# VisualightMicroDIY_03_gnd.net
KiCad netlist of a schematic drawn in EAGLE
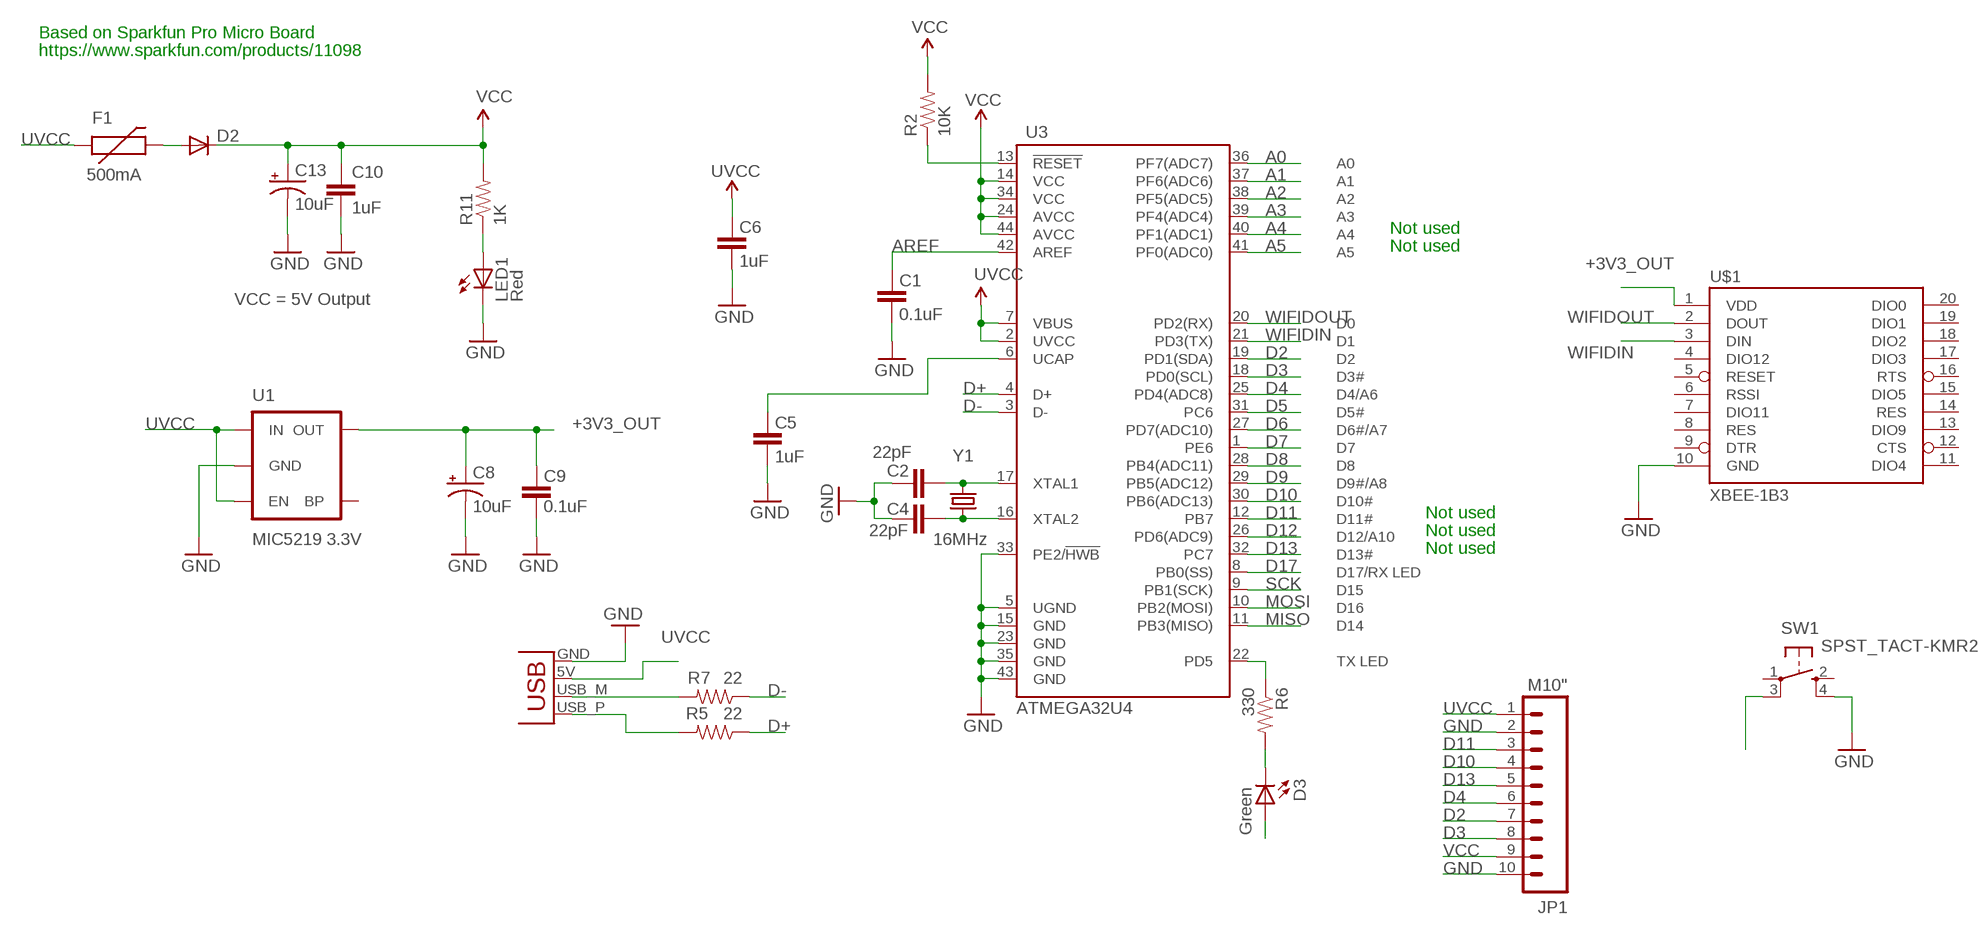
[diagram p0: schematic, sheet 1]

(export (version "E")
  (design (tool "Eeschema 10.0.6"))
  (components
    (comp (ref "C1")
      (value "0.1uF")
      (footprint "eagle-import:0402-CAP")
      (libsource (lib "eagle-import") (part "CAP0402-CAP"))
    )
    (comp (ref "C2")
      (value "22pF")
      (footprint "eagle-import:0402-CAP")
      (libsource (lib "eagle-import") (part "CAP0402-CAP"))
    )
    (comp (ref "C4")
      (value "22pF")
      (footprint "eagle-import:0402-CAP")
      (libsource (lib "eagle-import") (part "CAP0402-CAP"))
    )
    (comp (ref "C5")
      (value "1uF")
      (footprint "eagle-import:0402-CAP")
      (libsource (lib "eagle-import") (part "CAP0402-CAP"))
    )
    (comp (ref "C6")
      (value "1uF")
      (footprint "eagle-import:0402-CAP")
      (libsource (lib "eagle-import") (part "CAP0402-CAP"))
    )
    (comp (ref "C8")
      (value "10uF")
      (footprint "eagle-import:EIA3216")
      (libsource (lib "eagle-import") (part "CAP_POL1206"))
    )
    (comp (ref "C9")
      (value "0.1uF")
      (footprint "eagle-import:0402-CAP")
      (libsource (lib "eagle-import") (part "CAP0402-CAP"))
    )
    (comp (ref "C10")
      (value "1uF")
      (footprint "eagle-import:0402-CAP")
      (libsource (lib "eagle-import") (part "CAP0402-CAP"))
    )
    (comp (ref "C13")
      (value "10uF")
      (footprint "eagle-import:EIA3216")
      (libsource (lib "eagle-import") (part "CAP_POL1206"))
    )
    (comp (ref "D2")
      (value "DIODESOD")
      (footprint "eagle-import:SOD-323")
      (libsource (lib "eagle-import") (part "DIODESOD"))
    )
    (comp (ref "D3")
      (value "Green")
      (footprint "eagle-import:LED-0603")
      (libsource (lib "eagle-import") (part "LED0603"))
    )
    (comp (ref "F1")
      (value "500mA")
      (footprint "eagle-import:PTC-1206")
      (libsource (lib "eagle-import") (part "PTCSMD"))
    )
    (comp (ref "JP1")
      (value "M10\"")
      (footprint "eagle-import:1X10")
      (libsource (lib "eagle-import") (part "M10{dblquote}"))
    )
    (comp (ref "LED1")
      (value "Red")
      (footprint "eagle-import:LED-0603")
      (libsource (lib "eagle-import") (part "LED0603"))
    )
    (comp (ref "R2")
      (value "10K")
      (footprint "eagle-import:0402-RES")
      (libsource (lib "eagle-import") (part "RESISTOR0402-RES"))
    )
    (comp (ref "R5")
      (value "22")
      (footprint "eagle-import:0402-RES")
      (libsource (lib "eagle-import") (part "RESISTOR0402-RES"))
    )
    (comp (ref "R6")
      (value "330")
      (footprint "eagle-import:0402-RES")
      (libsource (lib "eagle-import") (part "RESISTOR0402-RES"))
    )
    (comp (ref "R7")
      (value "22")
      (footprint "eagle-import:0402-RES")
      (libsource (lib "eagle-import") (part "RESISTOR0402-RES"))
    )
    (comp (ref "R11")
      (value "1K")
      (footprint "eagle-import:0402-RES")
      (libsource (lib "eagle-import") (part "RESISTOR0402-RES"))
    )
    (comp (ref "SW1")
      (value "SPST_TACT-KMR2")
      (footprint "eagle-import:KMR2")
      (libsource (lib "eagle-import") (part "SPST_TACT-KMR2"))
    )
    (comp (ref "U$1")
      (value "XBEE-1B3")
      (footprint "eagle-import:XBEE-SMD")
      (libsource (lib "eagle-import") (part "XBEE-1B3"))
    )
    (comp (ref "U1")
      (value "MIC5219 3.3V")
      (footprint "eagle-import:SOT23-5")
      (libsource (lib "eagle-import") (part "V_REG_MIC52193.3V"))
    )
    (comp (ref "U3")
      (value "ATMEGA32U4")
      (footprint "eagle-import:SPARKFUN-DIGITALIC_TQFP44")
      (libsource (lib "eagle-import") (part "ATMEGA32U4TQFP"))
    )
    (comp (ref "X2")
      (value "USBPCB")
      (footprint "eagle-import:USB-A-PCB")
      (libsource (lib "eagle-import") (part "USBPCB"))
    )
    (comp (ref "Y1")
      (value "16MHz")
      (footprint "eagle-import:CRYSTAL-SMD-5X3")
      (libsource (lib "eagle-import") (part "CRYSTAL5X3"))
    )
  )
  (nets
    (net (code "1") (name "/+3V3_OUT") (class "Default")
      (node (ref "C8") (pin "A") (pinfunction "+_A") (pintype "passive"))
      (node (ref "C9") (pin "2") (pinfunction "2_2") (pintype "passive"))
      (node (ref "U$1") (pin "1") (pinfunction "VDD_1") (pintype "power_in"))
      (node (ref "U1") (pin "5") (pinfunction "OUT_5") (pintype "passive"))
    )
    (net (code "2") (name "/A0") (class "Default")
      (node (ref "U3") (pin "36") (pinfunction "PF7(ADC7)_36") (pintype "bidirectional"))
    )
    (net (code "3") (name "/A1") (class "Default")
      (node (ref "U3") (pin "37") (pinfunction "PF6(ADC6)_37") (pintype "bidirectional"))
    )
    (net (code "4") (name "/A2") (class "Default")
      (node (ref "U3") (pin "38") (pinfunction "PF5(ADC5)_38") (pintype "bidirectional"))
    )
    (net (code "5") (name "/A3") (class "Default")
      (node (ref "U3") (pin "39") (pinfunction "PF4(ADC4)_39") (pintype "bidirectional"))
    )
    (net (code "6") (name "/A4") (class "Default")
      (node (ref "U3") (pin "40") (pinfunction "PF1(ADC1)_40") (pintype "bidirectional"))
    )
    (net (code "7") (name "/A5") (class "Default")
      (node (ref "U3") (pin "41") (pinfunction "PF0(ADC0)_41") (pintype "bidirectional"))
    )
    (net (code "8") (name "/AREF") (class "Default")
      (node (ref "C1") (pin "2") (pinfunction "2_2") (pintype "passive"))
      (node (ref "U3") (pin "42") (pinfunction "AREF_42") (pintype "bidirectional"))
    )
    (net (code "9") (name "/D+") (class "Default")
      (node (ref "R5") (pin "1") (pinfunction "1_1") (pintype "passive"))
      (node (ref "U3") (pin "4") (pinfunction "D+_4") (pintype "bidirectional"))
    )
    (net (code "10") (name "/D-") (class "Default")
      (node (ref "R7") (pin "1") (pinfunction "1_1") (pintype "passive"))
      (node (ref "U3") (pin "3") (pinfunction "D-_3") (pintype "bidirectional"))
    )
    (net (code "11") (name "/D2") (class "Default")
      (node (ref "JP1") (pin "7") (pinfunction "7_7") (pintype "passive"))
      (node (ref "U3") (pin "19") (pinfunction "PD1(SDA)_19") (pintype "bidirectional"))
    )
    (net (code "12") (name "/D3") (class "Default")
      (node (ref "JP1") (pin "8") (pinfunction "8_8") (pintype "passive"))
      (node (ref "U3") (pin "18") (pinfunction "PD0(SCL)_18") (pintype "bidirectional"))
    )
    (net (code "13") (name "/D4") (class "Default")
      (node (ref "JP1") (pin "6") (pinfunction "6_6") (pintype "passive"))
      (node (ref "U3") (pin "25") (pinfunction "PD4(ADC8)_25") (pintype "bidirectional"))
    )
    (net (code "14") (name "/D5") (class "Default")
      (node (ref "U3") (pin "31") (pinfunction "PC6_31") (pintype "bidirectional"))
    )
    (net (code "15") (name "/D6") (class "Default")
      (node (ref "U3") (pin "27") (pinfunction "PD7(ADC10)_27") (pintype "bidirectional"))
    )
    (net (code "16") (name "/D7") (class "Default")
      (node (ref "SW1") (pin "3") (pinfunction "P1_3") (pintype "passive"))
      (node (ref "U3") (pin "1") (pinfunction "PE6_1") (pintype "bidirectional"))
    )
    (net (code "17") (name "/D8") (class "Default")
      (node (ref "U3") (pin "28") (pinfunction "PB4(ADC11)_28") (pintype "bidirectional"))
    )
    (net (code "18") (name "/D9") (class "Default")
      (node (ref "U3") (pin "29") (pinfunction "PB5(ADC12)_29") (pintype "bidirectional"))
    )
    (net (code "19") (name "/D10") (class "Default")
      (node (ref "JP1") (pin "4") (pinfunction "4_4") (pintype "passive"))
      (node (ref "U3") (pin "30") (pinfunction "PB6(ADC13)_30") (pintype "bidirectional"))
    )
    (net (code "20") (name "/D11") (class "Default")
      (node (ref "JP1") (pin "3") (pinfunction "3_3") (pintype "passive"))
      (node (ref "U3") (pin "12") (pinfunction "PB7_12") (pintype "bidirectional"))
    )
    (net (code "21") (name "/D12") (class "Default")
      (node (ref "U3") (pin "26") (pinfunction "PD6(ADC9)_26") (pintype "bidirectional"))
    )
    (net (code "22") (name "/D13") (class "Default")
      (node (ref "JP1") (pin "5") (pinfunction "5_5") (pintype "passive"))
      (node (ref "U3") (pin "32") (pinfunction "PC7_32") (pintype "bidirectional"))
    )
    (net (code "23") (name "/D17") (class "Default")
      (node (ref "U3") (pin "8") (pinfunction "PB0(SS)_8") (pintype "bidirectional"))
    )
    (net (code "24") (name "/MISO") (class "Default")
      (node (ref "U3") (pin "11") (pinfunction "PB3(MISO)_11") (pintype "bidirectional"))
    )
    (net (code "25") (name "/MOSI") (class "Default")
      (node (ref "U3") (pin "10") (pinfunction "PB2(MOSI)_10") (pintype "bidirectional"))
    )
    (net (code "26") (name "/SCK") (class "Default")
      (node (ref "U3") (pin "9") (pinfunction "PB1(SCK)_9") (pintype "bidirectional"))
    )
    (net (code "27") (name "/WIFIDIN") (class "Default")
      (node (ref "U$1") (pin "3") (pinfunction "DIN_3") (pintype "input"))
      (node (ref "U3") (pin "21") (pinfunction "PD3(TX)_21") (pintype "bidirectional"))
    )
    (net (code "28") (name "/WIFIDOUT") (class "Default")
      (node (ref "U$1") (pin "2") (pinfunction "DOUT_2") (pintype "output"))
      (node (ref "U3") (pin "20") (pinfunction "PD2(RX)_20") (pintype "bidirectional"))
    )
    (net (code "29") (name "GND") (class "Default")
      (node (ref "C1") (pin "1") (pinfunction "1_1") (pintype "passive"))
      (node (ref "C10") (pin "2") (pinfunction "2_2") (pintype "passive"))
      (node (ref "C13") (pin "C") (pinfunction "-_C") (pintype "passive"))
      (node (ref "C2") (pin "2") (pinfunction "2_2") (pintype "passive"))
      (node (ref "C4") (pin "2") (pinfunction "2_2") (pintype "passive"))
      (node (ref "C5") (pin "1") (pinfunction "1_1") (pintype "passive"))
      (node (ref "C6") (pin "1") (pinfunction "1_1") (pintype "passive"))
      (node (ref "C8") (pin "C") (pinfunction "-_C") (pintype "passive"))
      (node (ref "C9") (pin "1") (pinfunction "1_1") (pintype "passive"))
      (node (ref "JP1") (pin "10") (pinfunction "10_10") (pintype "passive"))
      (node (ref "JP1") (pin "2") (pinfunction "2_2") (pintype "passive"))
      (node (ref "LED1") (pin "C") (pinfunction "C_C") (pintype "passive"))
      (node (ref "SW1") (pin "4") (pinfunction "S1_4") (pintype "passive"))
      (node (ref "U$1") (pin "10") (pinfunction "GND_10") (pintype "power_in"))
      (node (ref "U1") (pin "2") (pinfunction "GND_2") (pintype "input"))
      (node (ref "U3") (pin "15") (pinfunction "GND_15") (pintype "bidirectional"))
      (node (ref "U3") (pin "23") (pinfunction "GND_23") (pintype "bidirectional"))
      (node (ref "U3") (pin "33") (pinfunction "PE2/~{HWB}_33") (pintype "bidirectional"))
      (node (ref "U3") (pin "35") (pinfunction "GND_35") (pintype "bidirectional"))
      (node (ref "U3") (pin "43") (pinfunction "GND_43") (pintype "bidirectional"))
      (node (ref "U3") (pin "5") (pinfunction "UGND_5") (pintype "bidirectional"))
      (node (ref "X2") (pin "GND") (pinfunction "GND_GND") (pintype "bidirectional"))
    )
    (net (code "30") (name "Net-(D2-A)") (class "Default")
      (node (ref "D2") (pin "2") (pinfunction "A_2") (pintype "passive"))
      (node (ref "F1") (pin "2") (pinfunction "2_2") (pintype "bidirectional"))
    )
    (net (code "31") (name "Net-(D3-PadC)") (class "Default")
      (node (ref "D3") (pin "C") (pinfunction "C_C") (pintype "passive"))
      (node (ref "R6") (pin "2") (pinfunction "2_2") (pintype "passive"))
    )
    (net (code "32") (name "Net-(LED1-PadA)") (class "Default")
      (node (ref "LED1") (pin "A") (pinfunction "A_A") (pintype "passive"))
      (node (ref "R11") (pin "1") (pinfunction "1_1") (pintype "passive"))
    )
    (net (code "33") (name "Net-(U3-PD5)") (class "Default")
      (node (ref "R6") (pin "1") (pinfunction "1_1") (pintype "passive"))
      (node (ref "U3") (pin "22") (pinfunction "PD5_22") (pintype "bidirectional"))
    )
    (net (code "34") (name "Net-(U3-UCAP)") (class "Default")
      (node (ref "C5") (pin "2") (pinfunction "2_2") (pintype "passive"))
      (node (ref "U3") (pin "6") (pinfunction "UCAP_6") (pintype "bidirectional"))
    )
    (net (code "35") (name "Net-(U3-XTAL1)") (class "Default")
      (node (ref "C2") (pin "1") (pinfunction "1_1") (pintype "passive"))
      (node (ref "U3") (pin "17") (pinfunction "XTAL1_17") (pintype "bidirectional"))
      (node (ref "Y1") (pin "3") (pinfunction "2_3") (pintype "passive"))
    )
    (net (code "36") (name "Net-(U3-XTAL2)") (class "Default")
      (node (ref "C4") (pin "1") (pinfunction "1_1") (pintype "passive"))
      (node (ref "U3") (pin "16") (pinfunction "XTAL2_16") (pintype "bidirectional"))
      (node (ref "Y1") (pin "1") (pinfunction "1_1") (pintype "passive"))
    )
    (net (code "37") (name "Net-(U3-~{RESET})") (class "Default")
      (node (ref "R2") (pin "1") (pinfunction "1_1") (pintype "passive"))
      (node (ref "U3") (pin "13") (pinfunction "~{RESET}_13") (pintype "bidirectional"))
    )
    (net (code "38") (name "Net-(X2-D+)") (class "Default")
      (node (ref "R5") (pin "2") (pinfunction "2_2") (pintype "passive"))
      (node (ref "X2") (pin "USB_P") (pinfunction "D+_USB_P") (pintype "bidirectional"))
    )
    (net (code "39") (name "Net-(X2-D-)") (class "Default")
      (node (ref "R7") (pin "2") (pinfunction "2_2") (pintype "passive"))
      (node (ref "X2") (pin "USB_M") (pinfunction "D-_USB_M") (pintype "bidirectional"))
    )
    (net (code "40") (name "UVCC") (class "Default")
      (node (ref "C6") (pin "2") (pinfunction "2_2") (pintype "passive"))
      (node (ref "D3") (pin "A") (pinfunction "A_A") (pintype "passive"))
      (node (ref "F1") (pin "1") (pinfunction "1_1") (pintype "bidirectional"))
      (node (ref "JP1") (pin "1") (pinfunction "1_1") (pintype "passive"))
      (node (ref "U1") (pin "1") (pinfunction "IN_1") (pintype "input"))
      (node (ref "U1") (pin "3") (pinfunction "EN_3") (pintype "input"))
      (node (ref "U3") (pin "2") (pinfunction "UVCC_2") (pintype "bidirectional"))
      (node (ref "U3") (pin "7") (pinfunction "VBUS_7") (pintype "bidirectional"))
      (node (ref "X2") (pin "5V") (pinfunction "VBUS_5V") (pintype "bidirectional"))
    )
    (net (code "41") (name "VCC") (class "Default")
      (node (ref "C10") (pin "1") (pinfunction "1_1") (pintype "passive"))
      (node (ref "C13") (pin "A") (pinfunction "+_A") (pintype "passive"))
      (node (ref "D2") (pin "1") (pinfunction "C_1") (pintype "passive"))
      (node (ref "JP1") (pin "9") (pinfunction "9_9") (pintype "passive"))
      (node (ref "R11") (pin "2") (pinfunction "2_2") (pintype "passive"))
      (node (ref "R2") (pin "2") (pinfunction "2_2") (pintype "passive"))
      (node (ref "U3") (pin "14") (pinfunction "VCC_14") (pintype "bidirectional"))
      (node (ref "U3") (pin "24") (pinfunction "AVCC_24") (pintype "bidirectional"))
      (node (ref "U3") (pin "34") (pinfunction "VCC_34") (pintype "bidirectional"))
      (node (ref "U3") (pin "44") (pinfunction "AVCC_44") (pintype "bidirectional"))
    )
    (net (code "42") (name "unconnected-(SW1-P-Pad1)") (class "Default")
      (node (ref "SW1") (pin "1") (pinfunction "P_1") (pintype "passive"))
    )
    (net (code "43") (name "unconnected-(SW1-S-Pad2)") (class "Default")
      (node (ref "SW1") (pin "2") (pinfunction "S_2") (pintype "passive"))
    )
    (net (code "44") (name "unconnected-(U$1-CTS-Pad12)") (class "Default")
      (node (ref "U$1") (pin "12") (pinfunction "CTS_12") (pintype "output"))
    )
    (net (code "45") (name "unconnected-(U$1-DIO0-Pad20)") (class "Default")
      (node (ref "U$1") (pin "20") (pinfunction "DIO0_20") (pintype "bidirectional"))
    )
    (net (code "46") (name "unconnected-(U$1-DIO1-Pad19)") (class "Default")
      (node (ref "U$1") (pin "19") (pinfunction "DIO1_19") (pintype "bidirectional"))
    )
    (net (code "47") (name "unconnected-(U$1-DIO2-Pad18)") (class "Default")
      (node (ref "U$1") (pin "18") (pinfunction "DIO2_18") (pintype "bidirectional"))
    )
    (net (code "48") (name "unconnected-(U$1-DIO3-Pad17)") (class "Default")
      (node (ref "U$1") (pin "17") (pinfunction "DIO3_17") (pintype "bidirectional"))
    )
    (net (code "49") (name "unconnected-(U$1-DIO4-Pad11)") (class "Default")
      (node (ref "U$1") (pin "11") (pinfunction "DIO4_11") (pintype "bidirectional"))
    )
    (net (code "50") (name "unconnected-(U$1-DIO5-Pad15)") (class "Default")
      (node (ref "U$1") (pin "15") (pinfunction "DIO5_15") (pintype "bidirectional"))
    )
    (net (code "51") (name "unconnected-(U$1-DIO9-Pad13)") (class "Default")
      (node (ref "U$1") (pin "13") (pinfunction "DIO9_13") (pintype "bidirectional"))
    )
    (net (code "52") (name "unconnected-(U$1-DIO11-Pad7)") (class "Default")
      (node (ref "U$1") (pin "7") (pinfunction "DIO11_7") (pintype "bidirectional"))
    )
    (net (code "53") (name "unconnected-(U$1-DIO12-Pad4)") (class "Default")
      (node (ref "U$1") (pin "4") (pinfunction "DIO12_4") (pintype "bidirectional"))
    )
    (net (code "54") (name "unconnected-(U$1-DTR-Pad9)") (class "Default")
      (node (ref "U$1") (pin "9") (pinfunction "DTR_9") (pintype "bidirectional"))
    )
    (net (code "55") (name "unconnected-(U$1-RES-Pad8)") (class "Default")
      (node (ref "U$1") (pin "8") (pinfunction "RES_8") (pintype "bidirectional"))
    )
    (net (code "56") (name "unconnected-(U$1-RES-Pad14)") (class "Default")
      (node (ref "U$1") (pin "14") (pinfunction "RES_14") (pintype "bidirectional"))
    )
    (net (code "57") (name "unconnected-(U$1-RESET-Pad5)") (class "Default")
      (node (ref "U$1") (pin "5") (pinfunction "RESET_5") (pintype "input"))
    )
    (net (code "58") (name "unconnected-(U$1-RSSI-Pad6)") (class "Default")
      (node (ref "U$1") (pin "6") (pinfunction "RSSI_6") (pintype "bidirectional"))
    )
    (net (code "59") (name "unconnected-(U$1-RTS-Pad16)") (class "Default")
      (node (ref "U$1") (pin "16") (pinfunction "RTS_16") (pintype "input"))
    )
    (net (code "60") (name "unconnected-(U1-BP-Pad4)") (class "Default")
      (node (ref "U1") (pin "4") (pinfunction "BP_4") (pintype "input"))
    )
  )
)
